# Growbox2.net
KiCad netlist of a schematic drawn in EAGLE
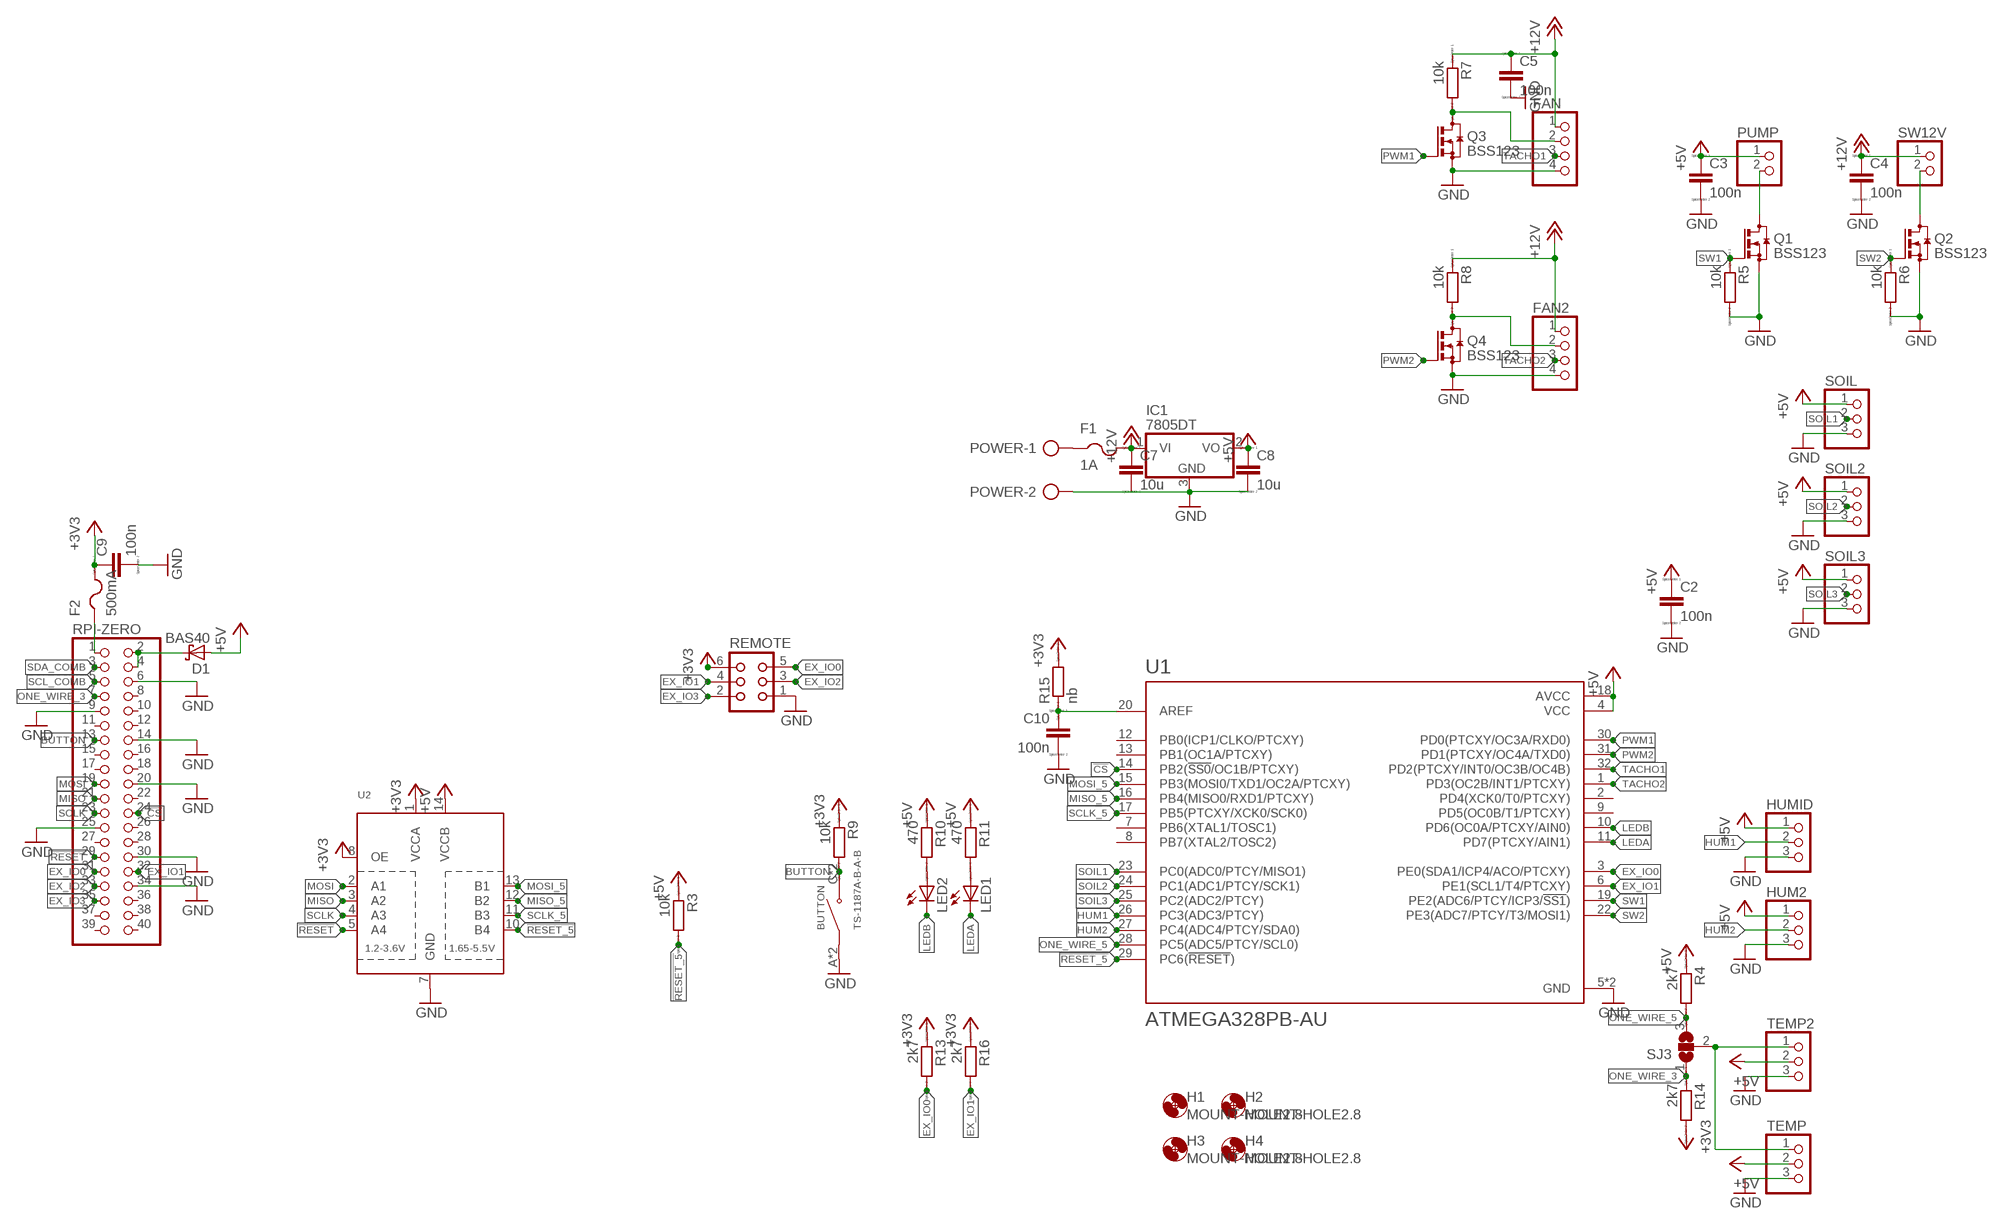
[diagram p0: schematic, sheet 1]

(export (version "E")
  (design (tool "Eeschema 10.0.6"))
  (components
    (comp (ref "BUTTON")
      (value "TS-1187A-B-A-B")
      (footprint "eagle-import:SW_TS-1187A-B-A-B")
      (fields (field (name "MF") "XKB Industrial Precision"))
      (libsource (lib "eagle-import") (part "TS-1187A-B-A-B"))
    )
    (comp (ref "C2")
      (value "100n")
      (footprint "eagle-import:C0603")
      (libsource (lib "eagle-import") (part "CC0603"))
    )
    (comp (ref "C3")
      (value "100n")
      (footprint "eagle-import:C0603")
      (libsource (lib "eagle-import") (part "CC0603"))
    )
    (comp (ref "C4")
      (value "100n")
      (footprint "eagle-import:C0603")
      (libsource (lib "eagle-import") (part "CC0603"))
    )
    (comp (ref "C5")
      (value "100n")
      (footprint "eagle-import:C0603")
      (libsource (lib "eagle-import") (part "CC0603"))
    )
    (comp (ref "C7")
      (value "10u")
      (footprint "eagle-import:C0603")
      (libsource (lib "eagle-import") (part "CC0603"))
    )
    (comp (ref "C8")
      (value "10u")
      (footprint "eagle-import:C0603")
      (libsource (lib "eagle-import") (part "CC0603"))
    )
    (comp (ref "C9")
      (value "100n")
      (footprint "eagle-import:C0603")
      (libsource (lib "eagle-import") (part "CC0603"))
    )
    (comp (ref "C10")
      (value "100n")
      (footprint "eagle-import:C0603")
      (libsource (lib "eagle-import") (part "CC0603"))
    )
    (comp (ref "D1")
      (value "BAS40")
      (footprint "eagle-import:SOT23")
      (libsource (lib "eagle-import") (part "BAS40"))
    )
    (comp (ref "F1")
      (value "1A")
      (footprint "eagle-import:R1206")
      (libsource (lib "eagle-import") (part "PTCFUSE-1206"))
    )
    (comp (ref "F2")
      (value "500mA")
      (footprint "eagle-import:R1206")
      (libsource (lib "eagle-import") (part "PTCFUSE-1206"))
    )
    (comp (ref "FAN")
      (value "PINHD-1X4")
      (footprint "eagle-import:1X04")
      (libsource (lib "eagle-import") (part "PINHD-1X4"))
    )
    (comp (ref "FAN2")
      (value "PINHD-1X4")
      (footprint "eagle-import:1X04")
      (libsource (lib "eagle-import") (part "PINHD-1X4"))
    )
    (comp (ref "H1")
      (value "MOUNT-HOLE2.8")
      (footprint "eagle-import:2,8")
      (libsource (lib "eagle-import") (part "MOUNT-HOLE2.8"))
    )
    (comp (ref "H2")
      (value "MOUNT-HOLE2.8")
      (footprint "eagle-import:2,8")
      (libsource (lib "eagle-import") (part "MOUNT-HOLE2.8"))
    )
    (comp (ref "H3")
      (value "MOUNT-HOLE2.8")
      (footprint "eagle-import:2,8")
      (libsource (lib "eagle-import") (part "MOUNT-HOLE2.8"))
    )
    (comp (ref "H4")
      (value "MOUNT-HOLE2.8")
      (footprint "eagle-import:2,8")
      (libsource (lib "eagle-import") (part "MOUNT-HOLE2.8"))
    )
    (comp (ref "HUM2")
      (value "PINHD-1X3")
      (footprint "eagle-import:1X03")
      (libsource (lib "eagle-import") (part "PINHD-1X3"))
    )
    (comp (ref "HUMID")
      (value "PINHD-1X3")
      (footprint "eagle-import:1X03")
      (libsource (lib "eagle-import") (part "PINHD-1X3"))
    )
    (comp (ref "IC1")
      (value "7805DT")
      (footprint "eagle-import:TO252")
      (libsource (lib "eagle-import") (part "78DT05"))
    )
    (comp (ref "LED1")
      (value "LEDCHIP-LED0603")
      (footprint "eagle-import:CHIP-LED0603")
      (libsource (lib "eagle-import") (part "LEDCHIP-LED0603"))
    )
    (comp (ref "LED2")
      (value "LEDCHIP-LED0603")
      (footprint "eagle-import:CHIP-LED0603")
      (libsource (lib "eagle-import") (part "LEDCHIP-LED0603"))
    )
    (comp (ref "POWER")
      (value "AK300/2")
      (footprint "eagle-import:AK300_2")
      (libsource (lib "eagle-import") (part "AK300/2"))
    )
    (comp (ref "PUMP")
      (value "PINHD-1X2")
      (footprint "eagle-import:1X02")
      (libsource (lib "eagle-import") (part "PINHD-1X2"))
    )
    (comp (ref "Q1")
      (value "BSS123")
      (footprint "eagle-import:SOT23")
      (libsource (lib "eagle-import") (part "BSS123"))
    )
    (comp (ref "Q2")
      (value "BSS123")
      (footprint "eagle-import:SOT23")
      (libsource (lib "eagle-import") (part "BSS123"))
    )
    (comp (ref "Q3")
      (value "BSS123")
      (footprint "eagle-import:SOT23")
      (libsource (lib "eagle-import") (part "BSS123"))
    )
    (comp (ref "Q4")
      (value "BSS123")
      (footprint "eagle-import:SOT23")
      (libsource (lib "eagle-import") (part "BSS123"))
    )
    (comp (ref "R3")
      (value "10k")
      (footprint "eagle-import:R0603")
      (libsource (lib "eagle-import") (part "RR0603"))
    )
    (comp (ref "R4")
      (value "2k7")
      (footprint "eagle-import:R0603")
      (libsource (lib "eagle-import") (part "RR0603"))
    )
    (comp (ref "R5")
      (value "10k")
      (footprint "eagle-import:R0603")
      (libsource (lib "eagle-import") (part "RR0603"))
    )
    (comp (ref "R6")
      (value "10k")
      (footprint "eagle-import:R0603")
      (libsource (lib "eagle-import") (part "RR0603"))
    )
    (comp (ref "R7")
      (value "10k")
      (footprint "eagle-import:R0603")
      (libsource (lib "eagle-import") (part "RR0603"))
    )
    (comp (ref "R8")
      (value "10k")
      (footprint "eagle-import:R0603")
      (libsource (lib "eagle-import") (part "RR0603"))
    )
    (comp (ref "R9")
      (value "10k")
      (footprint "eagle-import:R0603")
      (libsource (lib "eagle-import") (part "RR0603"))
    )
    (comp (ref "R10")
      (value "470")
      (footprint "eagle-import:R0603")
      (libsource (lib "eagle-import") (part "RR0603"))
    )
    (comp (ref "R11")
      (value "470")
      (footprint "eagle-import:R0603")
      (libsource (lib "eagle-import") (part "RR0603"))
    )
    (comp (ref "R13")
      (value "2k7")
      (footprint "eagle-import:R0603")
      (libsource (lib "eagle-import") (part "RR0603"))
    )
    (comp (ref "R14")
      (value "2k7")
      (footprint "eagle-import:R0603")
      (libsource (lib "eagle-import") (part "RR0603"))
    )
    (comp (ref "R15")
      (value "nb")
      (footprint "eagle-import:R0603")
      (libsource (lib "eagle-import") (part "RR0603"))
    )
    (comp (ref "R16")
      (value "2k7")
      (footprint "eagle-import:R0603")
      (libsource (lib "eagle-import") (part "RR0603"))
    )
    (comp (ref "REMOTE")
      (value "CON06")
      (footprint "eagle-import:CON06")
      (libsource (lib "eagle-import") (part "CON06"))
    )
    (comp (ref "RPI-ZERO")
      (value "PINHD-2X20")
      (footprint "eagle-import:2X20")
      (libsource (lib "eagle-import") (part "PINHD-2X20"))
    )
    (comp (ref "SJ3")
      (value "SJ2W")
      (footprint "eagle-import:SJ_2")
      (libsource (lib "eagle-import") (part "SJ2W"))
    )
    (comp (ref "SOIL")
      (value "PINHD-1X3")
      (footprint "eagle-import:1X03")
      (libsource (lib "eagle-import") (part "PINHD-1X3"))
    )
    (comp (ref "SOIL2")
      (value "PINHD-1X3")
      (footprint "eagle-import:1X03")
      (libsource (lib "eagle-import") (part "PINHD-1X3"))
    )
    (comp (ref "SOIL3")
      (value "PINHD-1X3")
      (footprint "eagle-import:1X03")
      (libsource (lib "eagle-import") (part "PINHD-1X3"))
    )
    (comp (ref "SW12V")
      (value "PINHD-1X2")
      (footprint "eagle-import:1X02")
      (libsource (lib "eagle-import") (part "PINHD-1X2"))
    )
    (comp (ref "TEMP")
      (value "PINHD-1X3")
      (footprint "eagle-import:1X03")
      (libsource (lib "eagle-import") (part "PINHD-1X3"))
    )
    (comp (ref "TEMP2")
      (value "PINHD-1X3")
      (footprint "eagle-import:1X03")
      (libsource (lib "eagle-import") (part "PINHD-1X3"))
    )
    (comp (ref "U1")
      (value "ATMEGA328PB-AU")
      (footprint "eagle-import:QFP80P900X900X120-32N")
      (fields (field (name "MF") "Microchip"))
      (libsource (lib "eagle-import") (part "ATMEGA328PB-AU"))
    )
    (comp (ref "U2")
      (value "TXB0104PWR")
      (footprint "eagle-import:TSSOP14")
      (libsource (lib "eagle-import") (part "TXB0104PWR"))
    )
  )
  (nets
    (net (code "1") (name "+3V3") (class "Default")
      (node (ref "C9") (pin "1") (pinfunction "1_1") (pintype "passive"))
      (node (ref "F2") (pin "2") (pinfunction "2_2") (pintype "passive"))
      (node (ref "R13") (pin "1") (pinfunction "1_1") (pintype "passive"))
      (node (ref "R14") (pin "2") (pinfunction "2_2") (pintype "passive"))
      (node (ref "R15") (pin "2") (pinfunction "2_2") (pintype "passive"))
      (node (ref "R16") (pin "1") (pinfunction "1_1") (pintype "passive"))
      (node (ref "R9") (pin "1") (pinfunction "1_1") (pintype "passive"))
      (node (ref "REMOTE") (pin "6") (pinfunction "6_6") (pintype "passive"))
      (node (ref "U2") (pin "1") (pinfunction "VCCA_1") (pintype "bidirectional"))
      (node (ref "U2") (pin "8") (pinfunction "OE_8") (pintype "bidirectional"))
    )
    (net (code "2") (name "+5V") (class "Default")
      (node (ref "C2") (pin "1") (pinfunction "1_1") (pintype "passive"))
      (node (ref "C3") (pin "1") (pinfunction "1_1") (pintype "passive"))
      (node (ref "C8") (pin "1") (pinfunction "1_1") (pintype "passive"))
      (node (ref "D1") (pin "1") (pinfunction "A_1") (pintype "passive"))
      (node (ref "HUM2") (pin "1") (pinfunction "1_1") (pintype "passive"))
      (node (ref "HUMID") (pin "1") (pinfunction "1_1") (pintype "passive"))
      (node (ref "IC1") (pin "2") (pinfunction "VO_2") (pintype "passive"))
      (node (ref "PUMP") (pin "1") (pinfunction "1_1") (pintype "passive"))
      (node (ref "R10") (pin "1") (pinfunction "1_1") (pintype "passive"))
      (node (ref "R11") (pin "1") (pinfunction "1_1") (pintype "passive"))
      (node (ref "R3") (pin "1") (pinfunction "1_1") (pintype "passive"))
      (node (ref "R4") (pin "1") (pinfunction "1_1") (pintype "passive"))
      (node (ref "SOIL") (pin "1") (pinfunction "1_1") (pintype "passive"))
      (node (ref "SOIL2") (pin "1") (pinfunction "1_1") (pintype "passive"))
      (node (ref "SOIL3") (pin "1") (pinfunction "1_1") (pintype "passive"))
      (node (ref "TEMP") (pin "2") (pinfunction "2_2") (pintype "passive"))
      (node (ref "TEMP2") (pin "2") (pinfunction "2_2") (pintype "passive"))
      (node (ref "U1") (pin "18") (pinfunction "AVCC_18") (pintype "power_in"))
      (node (ref "U1") (pin "4") (pinfunction "VCC_4") (pintype "power_in"))
      (node (ref "U2") (pin "14") (pinfunction "VCCB_14") (pintype "bidirectional"))
    )
    (net (code "3") (name "+12V") (class "Default")
      (node (ref "C4") (pin "1") (pinfunction "1_1") (pintype "passive"))
      (node (ref "C5") (pin "1") (pinfunction "1_1") (pintype "passive"))
      (node (ref "C7") (pin "1") (pinfunction "1_1") (pintype "passive"))
      (node (ref "F1") (pin "2") (pinfunction "2_2") (pintype "passive"))
      (node (ref "FAN") (pin "1") (pinfunction "1_1") (pintype "passive"))
      (node (ref "FAN2") (pin "1") (pinfunction "1_1") (pintype "passive"))
      (node (ref "IC1") (pin "1") (pinfunction "VI_1") (pintype "input"))
      (node (ref "R7") (pin "1") (pinfunction "1_1") (pintype "passive"))
      (node (ref "R8") (pin "1") (pinfunction "1_1") (pintype "passive"))
      (node (ref "SW12V") (pin "1") (pinfunction "1_1") (pintype "passive"))
    )
    (net (code "4") (name "/~{CS}") (class "Default")
      (node (ref "RPI-ZERO") (pin "24") (pinfunction "24_24") (pintype "passive"))
      (node (ref "U1") (pin "14") (pinfunction "PB2(~{SS0}/OC1B/PTCXY)_14") (pintype "bidirectional"))
    )
    (net (code "5") (name "/~{RESET_5}") (class "Default")
      (node (ref "R3") (pin "2") (pinfunction "2_2") (pintype "passive"))
      (node (ref "U1") (pin "29") (pinfunction "PC6(~{RESET})_29") (pintype "bidirectional"))
      (node (ref "U2") (pin "10") (pinfunction "B4_10") (pintype "bidirectional"))
    )
    (net (code "6") (name "/~{RESET}") (class "Default")
      (node (ref "RPI-ZERO") (pin "29") (pinfunction "29_29") (pintype "passive"))
      (node (ref "U2") (pin "5") (pinfunction "A4_5") (pintype "bidirectional"))
    )
    (net (code "7") (name "BUTTON") (class "Default")
      (node (ref "BUTTON") (pin "C") (pinfunction "NO_C") (pintype "passive"))
      (node (ref "BUTTON") (pin "D") (pinfunction "NO_D") (pintype "passive"))
      (node (ref "R9") (pin "2") (pinfunction "2_2") (pintype "passive"))
      (node (ref "RPI-ZERO") (pin "13") (pinfunction "13_13") (pintype "passive"))
    )
    (net (code "8") (name "EX_IO0") (class "Default")
      (node (ref "R13") (pin "2") (pinfunction "2_2") (pintype "passive"))
      (node (ref "REMOTE") (pin "5") (pinfunction "5_5") (pintype "passive"))
      (node (ref "RPI-ZERO") (pin "31") (pinfunction "31_31") (pintype "passive"))
      (node (ref "U1") (pin "3") (pinfunction "PE0(SDA1/ICP4/ACO/PTCXY)_3") (pintype "bidirectional"))
    )
    (net (code "9") (name "EX_IO1") (class "Default")
      (node (ref "R16") (pin "2") (pinfunction "2_2") (pintype "passive"))
      (node (ref "REMOTE") (pin "4") (pinfunction "4_4") (pintype "passive"))
      (node (ref "RPI-ZERO") (pin "32") (pinfunction "32_32") (pintype "passive"))
      (node (ref "U1") (pin "6") (pinfunction "PE1(SCL1/T4/PTCXY)_6") (pintype "bidirectional"))
    )
    (net (code "10") (name "EX_IO2") (class "Default")
      (node (ref "REMOTE") (pin "3") (pinfunction "3_3") (pintype "passive"))
      (node (ref "RPI-ZERO") (pin "33") (pinfunction "33_33") (pintype "passive"))
    )
    (net (code "11") (name "EX_IO3") (class "Default")
      (node (ref "REMOTE") (pin "2") (pinfunction "2_2") (pintype "passive"))
      (node (ref "RPI-ZERO") (pin "35") (pinfunction "35_35") (pintype "passive"))
    )
    (net (code "12") (name "GND") (class "Default")
      (node (ref "BUTTON") (pin "A") (pinfunction "COM_A") (pintype "passive"))
      (node (ref "BUTTON") (pin "B") (pinfunction "COM_B") (pintype "passive"))
      (node (ref "C10") (pin "2") (pinfunction "2_2") (pintype "passive"))
      (node (ref "C2") (pin "2") (pinfunction "2_2") (pintype "passive"))
      (node (ref "C3") (pin "2") (pinfunction "2_2") (pintype "passive"))
      (node (ref "C4") (pin "2") (pinfunction "2_2") (pintype "passive"))
      (node (ref "C5") (pin "2") (pinfunction "2_2") (pintype "passive"))
      (node (ref "C7") (pin "2") (pinfunction "2_2") (pintype "passive"))
      (node (ref "C8") (pin "2") (pinfunction "2_2") (pintype "passive"))
      (node (ref "C9") (pin "2") (pinfunction "2_2") (pintype "passive"))
      (node (ref "FAN") (pin "4") (pinfunction "4_4") (pintype "passive"))
      (node (ref "FAN2") (pin "4") (pinfunction "4_4") (pintype "passive"))
      (node (ref "HUM2") (pin "3") (pinfunction "3_3") (pintype "passive"))
      (node (ref "HUMID") (pin "3") (pinfunction "3_3") (pintype "passive"))
      (node (ref "IC1") (pin "3") (pinfunction "GND_3") (pintype "passive"))
      (node (ref "POWER") (pin "2") (pinfunction "KL_2") (pintype "passive"))
      (node (ref "Q1") (pin "2") (pinfunction "S_2") (pintype "passive"))
      (node (ref "Q2") (pin "2") (pinfunction "S_2") (pintype "passive"))
      (node (ref "Q3") (pin "2") (pinfunction "S_2") (pintype "passive"))
      (node (ref "Q4") (pin "2") (pinfunction "S_2") (pintype "passive"))
      (node (ref "R5") (pin "2") (pinfunction "2_2") (pintype "passive"))
      (node (ref "R6") (pin "2") (pinfunction "2_2") (pintype "passive"))
      (node (ref "REMOTE") (pin "1") (pinfunction "1_1") (pintype "passive"))
      (node (ref "RPI-ZERO") (pin "14") (pinfunction "14_14") (pintype "passive"))
      (node (ref "RPI-ZERO") (pin "20") (pinfunction "20_20") (pintype "passive"))
      (node (ref "RPI-ZERO") (pin "25") (pinfunction "25_25") (pintype "passive"))
      (node (ref "RPI-ZERO") (pin "30") (pinfunction "30_30") (pintype "passive"))
      (node (ref "RPI-ZERO") (pin "34") (pinfunction "34_34") (pintype "passive"))
      (node (ref "RPI-ZERO") (pin "6") (pinfunction "6_6") (pintype "passive"))
      (node (ref "RPI-ZERO") (pin "9") (pinfunction "9_9") (pintype "passive"))
      (node (ref "SOIL") (pin "3") (pinfunction "3_3") (pintype "passive"))
      (node (ref "SOIL2") (pin "3") (pinfunction "3_3") (pintype "passive"))
      (node (ref "SOIL3") (pin "3") (pinfunction "3_3") (pintype "passive"))
      (node (ref "TEMP") (pin "3") (pinfunction "3_3") (pintype "passive"))
      (node (ref "TEMP2") (pin "3") (pinfunction "3_3") (pintype "passive"))
      (node (ref "U1") (pin "21") (pinfunction "GND_21") (pintype "power_in"))
      (node (ref "U1") (pin "5") (pinfunction "GND_5") (pintype "power_in"))
      (node (ref "U2") (pin "7") (pinfunction "GND_7") (pintype "bidirectional"))
    )
    (net (code "13") (name "HUM1") (class "Default")
      (node (ref "HUMID") (pin "2") (pinfunction "2_2") (pintype "passive"))
      (node (ref "U1") (pin "26") (pinfunction "PC3(ADC3/PTCY)_26") (pintype "bidirectional"))
    )
    (net (code "14") (name "HUM2") (class "Default")
      (node (ref "HUM2") (pin "2") (pinfunction "2_2") (pintype "passive"))
      (node (ref "U1") (pin "27") (pinfunction "PC4(ADC4/PTCY/SDA0)_27") (pintype "bidirectional"))
    )
    (net (code "15") (name "LEDA") (class "Default")
      (node (ref "LED1") (pin "C") (pinfunction "C_C") (pintype "passive"))
      (node (ref "U1") (pin "11") (pinfunction "PD7(PTCXY/AIN1)_11") (pintype "bidirectional"))
    )
    (net (code "16") (name "LEDB") (class "Default")
      (node (ref "LED2") (pin "C") (pinfunction "C_C") (pintype "passive"))
      (node (ref "U1") (pin "10") (pinfunction "PD6(OC0A/PTCXY/AIN0)_10") (pintype "bidirectional"))
    )
    (net (code "17") (name "MISO") (class "Default")
      (node (ref "RPI-ZERO") (pin "21") (pinfunction "21_21") (pintype "passive"))
      (node (ref "U2") (pin "3") (pinfunction "A2_3") (pintype "bidirectional"))
    )
    (net (code "18") (name "MISO_5") (class "Default")
      (node (ref "U1") (pin "16") (pinfunction "PB4(MISO0/RXD1/PTCXY)_16") (pintype "bidirectional"))
      (node (ref "U2") (pin "12") (pinfunction "B2_12") (pintype "bidirectional"))
    )
    (net (code "19") (name "MOSI") (class "Default")
      (node (ref "RPI-ZERO") (pin "19") (pinfunction "19_19") (pintype "passive"))
      (node (ref "U2") (pin "2") (pinfunction "A1_2") (pintype "bidirectional"))
    )
    (net (code "20") (name "MOSI_5") (class "Default")
      (node (ref "U1") (pin "15") (pinfunction "PB3(MOSI0/TXD1/OC2A/PTCXY)_15") (pintype "bidirectional"))
      (node (ref "U2") (pin "13") (pinfunction "B1_13") (pintype "bidirectional"))
    )
    (net (code "21") (name "Net-(D1-C)") (class "Default")
      (node (ref "D1") (pin "3") (pinfunction "C_3") (pintype "passive"))
      (node (ref "RPI-ZERO") (pin "2") (pinfunction "2_2") (pintype "passive"))
      (node (ref "RPI-ZERO") (pin "4") (pinfunction "4_4") (pintype "passive"))
    )
    (net (code "22") (name "Net-(F2-Pad1)") (class "Default")
      (node (ref "F2") (pin "1") (pinfunction "1_1") (pintype "passive"))
      (node (ref "RPI-ZERO") (pin "1") (pinfunction "1_1") (pintype "passive"))
    )
    (net (code "23") (name "Net-(LED1-PadA)") (class "Default")
      (node (ref "LED1") (pin "A") (pinfunction "A_A") (pintype "passive"))
      (node (ref "R11") (pin "2") (pinfunction "2_2") (pintype "passive"))
    )
    (net (code "24") (name "Net-(LED2-PadA)") (class "Default")
      (node (ref "LED2") (pin "A") (pinfunction "A_A") (pintype "passive"))
      (node (ref "R10") (pin "2") (pinfunction "2_2") (pintype "passive"))
    )
    (net (code "25") (name "Net-(POWERA-KL)") (class "Default")
      (node (ref "F1") (pin "1") (pinfunction "1_1") (pintype "passive"))
      (node (ref "POWER") (pin "1") (pinfunction "KL_1") (pintype "passive"))
    )
    (net (code "26") (name "Net-(Q1-D)") (class "Default")
      (node (ref "PUMP") (pin "2") (pinfunction "2_2") (pintype "passive"))
      (node (ref "Q1") (pin "3") (pinfunction "D_3") (pintype "passive"))
    )
    (net (code "27") (name "Net-(Q2-D)") (class "Default")
      (node (ref "Q2") (pin "3") (pinfunction "D_3") (pintype "passive"))
      (node (ref "SW12V") (pin "2") (pinfunction "2_2") (pintype "passive"))
    )
    (net (code "28") (name "Net-(Q3-D)") (class "Default")
      (node (ref "FAN") (pin "2") (pinfunction "2_2") (pintype "passive"))
      (node (ref "Q3") (pin "3") (pinfunction "D_3") (pintype "passive"))
      (node (ref "R7") (pin "2") (pinfunction "2_2") (pintype "passive"))
    )
    (net (code "29") (name "Net-(Q4-D)") (class "Default")
      (node (ref "FAN2") (pin "2") (pinfunction "2_2") (pintype "passive"))
      (node (ref "Q4") (pin "3") (pinfunction "D_3") (pintype "passive"))
      (node (ref "R8") (pin "2") (pinfunction "2_2") (pintype "passive"))
    )
    (net (code "30") (name "Net-(SJ3-Pad2)") (class "Default")
      (node (ref "SJ3") (pin "2") (pinfunction "2_2") (pintype "passive"))
      (node (ref "TEMP") (pin "1") (pinfunction "1_1") (pintype "passive"))
      (node (ref "TEMP2") (pin "1") (pinfunction "1_1") (pintype "passive"))
    )
    (net (code "31") (name "Net-(U1-AREF)") (class "Default")
      (node (ref "C10") (pin "1") (pinfunction "1_1") (pintype "passive"))
      (node (ref "R15") (pin "1") (pinfunction "1_1") (pintype "passive"))
      (node (ref "U1") (pin "20") (pinfunction "AREF_20") (pintype "input"))
    )
    (net (code "32") (name "ONE_WIRE_3") (class "Default")
      (node (ref "R14") (pin "1") (pinfunction "1_1") (pintype "passive"))
      (node (ref "RPI-ZERO") (pin "7") (pinfunction "7_7") (pintype "passive"))
      (node (ref "SJ3") (pin "1") (pinfunction "1_1") (pintype "passive"))
    )
    (net (code "33") (name "ONE_WIRE_5") (class "Default")
      (node (ref "R4") (pin "2") (pinfunction "2_2") (pintype "passive"))
      (node (ref "SJ3") (pin "3") (pinfunction "3_3") (pintype "passive"))
      (node (ref "U1") (pin "28") (pinfunction "PC5(ADC5/PTCY/SCL0)_28") (pintype "bidirectional"))
    )
    (net (code "34") (name "PWM1") (class "Default")
      (node (ref "Q3") (pin "1") (pinfunction "G_1") (pintype "passive"))
      (node (ref "U1") (pin "30") (pinfunction "PD0(PTCXY/OC3A/RXD0)_30") (pintype "bidirectional"))
    )
    (net (code "35") (name "PWM2") (class "Default")
      (node (ref "Q4") (pin "1") (pinfunction "G_1") (pintype "passive"))
      (node (ref "U1") (pin "31") (pinfunction "PD1(PTCXY/OC4A/TXD0)_31") (pintype "bidirectional"))
    )
    (net (code "36") (name "SCLK") (class "Default")
      (node (ref "RPI-ZERO") (pin "23") (pinfunction "23_23") (pintype "passive"))
      (node (ref "U2") (pin "4") (pinfunction "A3_4") (pintype "bidirectional"))
    )
    (net (code "37") (name "SCLK_5") (class "Default")
      (node (ref "U1") (pin "17") (pinfunction "PB5(PTCXY/XCK0/SCK0)_17") (pintype "bidirectional"))
      (node (ref "U2") (pin "11") (pinfunction "B3_11") (pintype "bidirectional"))
    )
    (net (code "38") (name "SCL_COMB") (class "Default")
      (node (ref "RPI-ZERO") (pin "5") (pinfunction "5_5") (pintype "passive"))
    )
    (net (code "39") (name "SDA_COMB") (class "Default")
      (node (ref "RPI-ZERO") (pin "3") (pinfunction "3_3") (pintype "passive"))
    )
    (net (code "40") (name "SOIL1") (class "Default")
      (node (ref "SOIL") (pin "2") (pinfunction "2_2") (pintype "passive"))
      (node (ref "U1") (pin "23") (pinfunction "PC0(ADC0/PTCY/MISO1)_23") (pintype "bidirectional"))
    )
    (net (code "41") (name "SOIL2") (class "Default")
      (node (ref "SOIL2") (pin "2") (pinfunction "2_2") (pintype "passive"))
      (node (ref "U1") (pin "24") (pinfunction "PC1(ADC1/PTCY/SCK1)_24") (pintype "bidirectional"))
    )
    (net (code "42") (name "SOIL3") (class "Default")
      (node (ref "SOIL3") (pin "2") (pinfunction "2_2") (pintype "passive"))
      (node (ref "U1") (pin "25") (pinfunction "PC2(ADC2/PTCY)_25") (pintype "bidirectional"))
    )
    (net (code "43") (name "SW1") (class "Default")
      (node (ref "Q1") (pin "1") (pinfunction "G_1") (pintype "passive"))
      (node (ref "R5") (pin "1") (pinfunction "1_1") (pintype "passive"))
      (node (ref "U1") (pin "19") (pinfunction "PE2(ADC6/PTCY/ICP3/~{SS1})_19") (pintype "bidirectional"))
    )
    (net (code "44") (name "SW2") (class "Default")
      (node (ref "Q2") (pin "1") (pinfunction "G_1") (pintype "passive"))
      (node (ref "R6") (pin "1") (pinfunction "1_1") (pintype "passive"))
      (node (ref "U1") (pin "22") (pinfunction "PE3(ADC7/PTCY/T3/MOSI1)_22") (pintype "bidirectional"))
    )
    (net (code "45") (name "TACHO1") (class "Default")
      (node (ref "FAN") (pin "3") (pinfunction "3_3") (pintype "passive"))
      (node (ref "U1") (pin "32") (pinfunction "PD2(PTCXY/INT0/OC3B/OC4B)_32") (pintype "bidirectional"))
    )
    (net (code "46") (name "TACHO2") (class "Default")
      (node (ref "FAN2") (pin "3") (pinfunction "3_3") (pintype "passive"))
      (node (ref "U1") (pin "1") (pinfunction "PD3(OC2B/INT1/PTCXY)_1") (pintype "bidirectional"))
    )
    (net (code "47") (name "unconnected-(RPI-ZERO-Pad8)") (class "Default")
      (node (ref "RPI-ZERO") (pin "8") (pinfunction "8_8") (pintype "passive"))
    )
    (net (code "48") (name "unconnected-(RPI-ZERO-Pad10)") (class "Default")
      (node (ref "RPI-ZERO") (pin "10") (pinfunction "10_10") (pintype "passive"))
    )
    (net (code "49") (name "unconnected-(RPI-ZERO-Pad11)") (class "Default")
      (node (ref "RPI-ZERO") (pin "11") (pinfunction "11_11") (pintype "passive"))
    )
    (net (code "50") (name "unconnected-(RPI-ZERO-Pad12)") (class "Default")
      (node (ref "RPI-ZERO") (pin "12") (pinfunction "12_12") (pintype "passive"))
    )
    (net (code "51") (name "unconnected-(RPI-ZERO-Pad15)") (class "Default")
      (node (ref "RPI-ZERO") (pin "15") (pinfunction "15_15") (pintype "passive"))
    )
    (net (code "52") (name "unconnected-(RPI-ZERO-Pad16)") (class "Default")
      (node (ref "RPI-ZERO") (pin "16") (pinfunction "16_16") (pintype "passive"))
    )
    (net (code "53") (name "unconnected-(RPI-ZERO-Pad17)") (class "Default")
      (node (ref "RPI-ZERO") (pin "17") (pinfunction "17_17") (pintype "passive"))
    )
    (net (code "54") (name "unconnected-(RPI-ZERO-Pad18)") (class "Default")
      (node (ref "RPI-ZERO") (pin "18") (pinfunction "18_18") (pintype "passive"))
    )
    (net (code "55") (name "unconnected-(RPI-ZERO-Pad22)") (class "Default")
      (node (ref "RPI-ZERO") (pin "22") (pinfunction "22_22") (pintype "passive"))
    )
    (net (code "56") (name "unconnected-(RPI-ZERO-Pad26)") (class "Default")
      (node (ref "RPI-ZERO") (pin "26") (pinfunction "26_26") (pintype "passive"))
    )
    (net (code "57") (name "unconnected-(RPI-ZERO-Pad27)") (class "Default")
      (node (ref "RPI-ZERO") (pin "27") (pinfunction "27_27") (pintype "passive"))
    )
    (net (code "58") (name "unconnected-(RPI-ZERO-Pad28)") (class "Default")
      (node (ref "RPI-ZERO") (pin "28") (pinfunction "28_28") (pintype "passive"))
    )
    (net (code "59") (name "unconnected-(RPI-ZERO-Pad36)") (class "Default")
      (node (ref "RPI-ZERO") (pin "36") (pinfunction "36_36") (pintype "passive"))
    )
    (net (code "60") (name "unconnected-(RPI-ZERO-Pad37)") (class "Default")
      (node (ref "RPI-ZERO") (pin "37") (pinfunction "37_37") (pintype "passive"))
    )
    (net (code "61") (name "unconnected-(RPI-ZERO-Pad38)") (class "Default")
      (node (ref "RPI-ZERO") (pin "38") (pinfunction "38_38") (pintype "passive"))
    )
    (net (code "62") (name "unconnected-(RPI-ZERO-Pad39)") (class "Default")
      (node (ref "RPI-ZERO") (pin "39") (pinfunction "39_39") (pintype "passive"))
    )
    (net (code "63") (name "unconnected-(RPI-ZERO-Pad40)") (class "Default")
      (node (ref "RPI-ZERO") (pin "40") (pinfunction "40_40") (pintype "passive"))
    )
    (net (code "64") (name "unconnected-(U1-PB0(ICP1{slash}CLKO{slash}PTCXY)-Pad12)") (class "Default")
      (node (ref "U1") (pin "12") (pinfunction "PB0(ICP1/CLKO/PTCXY)_12") (pintype "bidirectional"))
    )
    (net (code "65") (name "unconnected-(U1-PB1(OC1A{slash}PTCXY)-Pad13)") (class "Default")
      (node (ref "U1") (pin "13") (pinfunction "PB1(OC1A/PTCXY)_13") (pintype "bidirectional"))
    )
    (net (code "66") (name "unconnected-(U1-PB6(XTAL1{slash}TOSC1)-Pad7)") (class "Default")
      (node (ref "U1") (pin "7") (pinfunction "PB6(XTAL1/TOSC1)_7") (pintype "bidirectional"))
    )
    (net (code "67") (name "unconnected-(U1-PB7(XTAL2{slash}TOSC2)-Pad8)") (class "Default")
      (node (ref "U1") (pin "8") (pinfunction "PB7(XTAL2/TOSC2)_8") (pintype "bidirectional"))
    )
    (net (code "68") (name "unconnected-(U1-PD4(XCK0{slash}T0{slash}PTCXY)-Pad2)") (class "Default")
      (node (ref "U1") (pin "2") (pinfunction "PD4(XCK0/T0/PTCXY)_2") (pintype "bidirectional"))
    )
    (net (code "69") (name "unconnected-(U1-PD5(OC0B{slash}T1{slash}PTCXY)-Pad9)") (class "Default")
      (node (ref "U1") (pin "9") (pinfunction "PD5(OC0B/T1/PTCXY)_9") (pintype "bidirectional"))
    )
  )
)
